# FuenteSim.net
KiCad netlist of a schematic drawn in Altium Designer
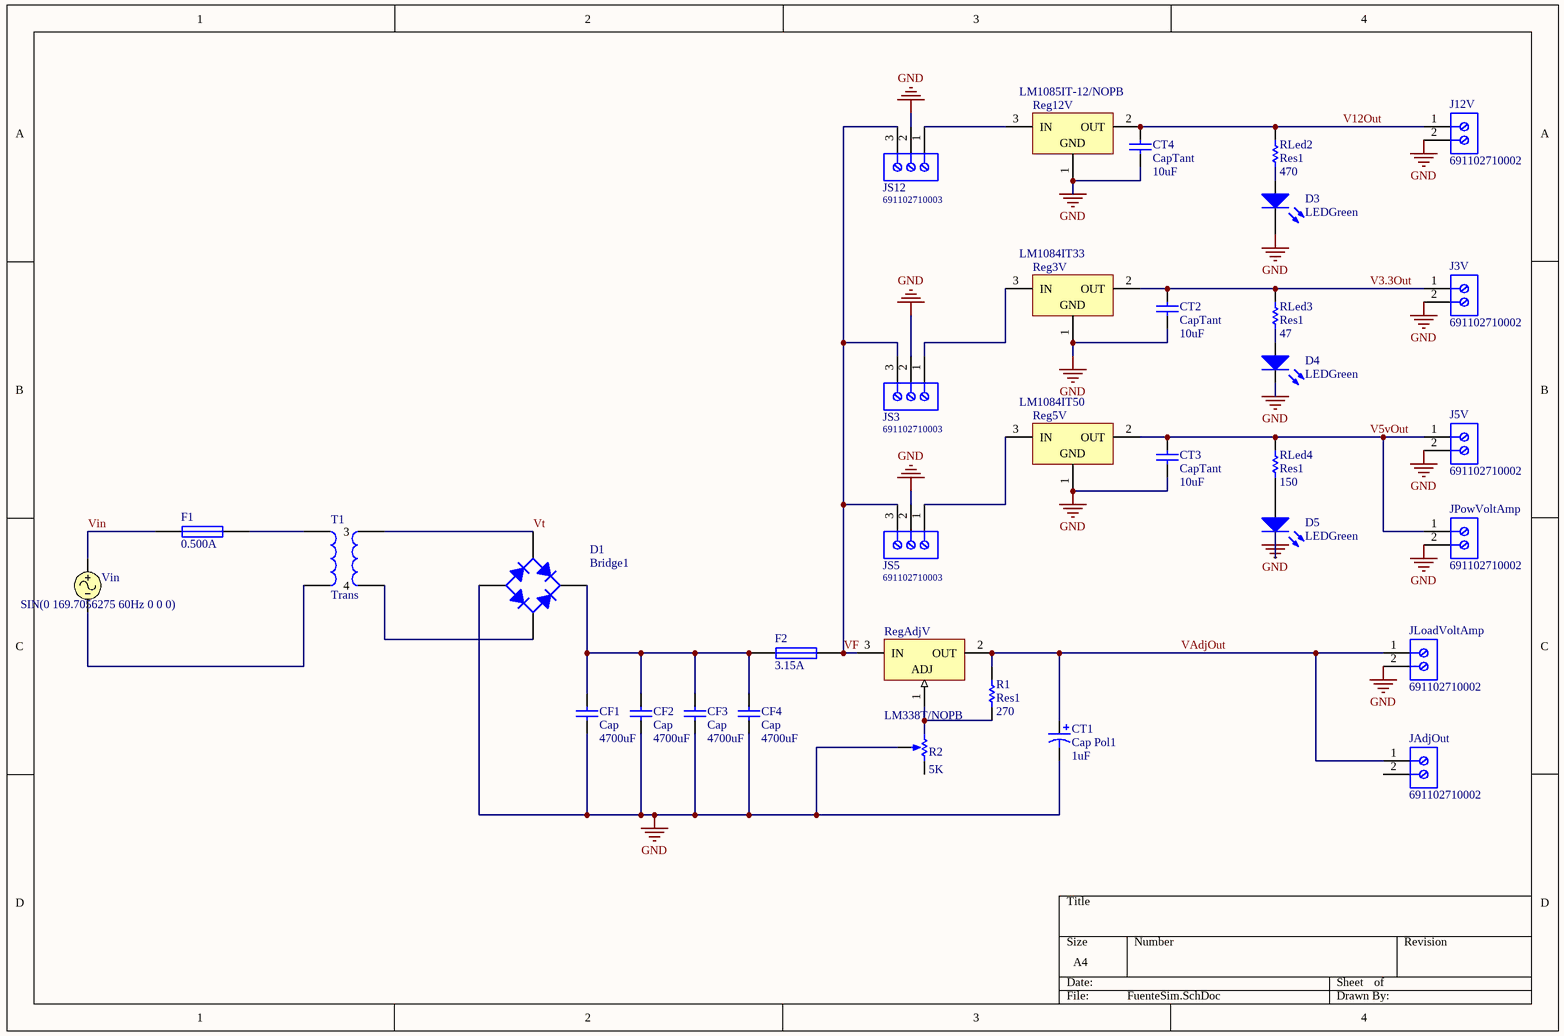
[diagram p0: FuenteSim.SchDoc]

(export (version "E")
  (design (tool "Eeschema 10.0.6"))
  (components
    (comp (ref "CF1")
      (value "Cap")
      (footprint "4700uF")
      (description "Capacitor")
      (fields (field (name "ALTIUM_VALUE") "4700uF") (field (name "PUBLISHER") "Altium Limited"))
      (libsource (lib "Miscellaneous Devices") (part "Cap"))
    )
    (comp (ref "CF2")
      (value "Cap")
      (footprint "4700uF")
      (description "Capacitor")
      (fields (field (name "ALTIUM_VALUE") "4700uF") (field (name "PUBLISHER") "Altium Limited"))
      (libsource (lib "Miscellaneous Devices") (part "Cap"))
    )
    (comp (ref "CF3")
      (value "Cap")
      (footprint "4700uF")
      (description "Capacitor")
      (fields (field (name "ALTIUM_VALUE") "4700uF") (field (name "PUBLISHER") "Altium Limited"))
      (libsource (lib "Miscellaneous Devices") (part "Cap"))
    )
    (comp (ref "CF4")
      (value "Cap")
      (footprint "4700uF")
      (description "Capacitor")
      (fields (field (name "ALTIUM_VALUE") "4700uF") (field (name "PUBLISHER") "Altium Limited"))
      (libsource (lib "Miscellaneous Devices") (part "Cap"))
    )
    (comp (ref "CT1")
      (value "Cap Pol1")
      (footprint "CAPPRD200W50D500H1250")
      (description "Polarized Capacitor (Radial)")
      (fields (field (name "ALTIUM_VALUE") "1uF") (field (name "PUBLISHER") "Altium Limited"))
      (libsource (lib "Miscellaneous Devices") (part "Cap Pol1"))
    )
    (comp (ref "CT2")
      (value "CapTant")
      (footprint "RAD-0.3")
      (description "Capacitor")
      (fields (field (name "ALTIUM_VALUE") "10uF") (field (name "PUBLISHER") "Altium Limited"))
      (libsource (lib "Miscellaneous Devices") (part "Cap"))
    )
    (comp (ref "CT3")
      (value "CapTant")
      (footprint "RAD-0.3")
      (description "Capacitor")
      (fields (field (name "ALTIUM_VALUE") "10uF") (field (name "PUBLISHER") "Altium Limited"))
      (libsource (lib "Miscellaneous Devices") (part "Cap"))
    )
    (comp (ref "CT4")
      (value "CapTant")
      (footprint "RAD-0.3")
      (description "Capacitor")
      (fields (field (name "ALTIUM_VALUE") "10uF") (field (name "PUBLISHER") "Altium Limited"))
      (libsource (lib "Miscellaneous Devices") (part "Cap"))
    )
    (comp (ref "D1")
      (value "Bridge1")
      (footprint "DIOB_GBJ2510")
      (description "Full Wave Diode Bridge")
      (fields (field (name "PUBLISHER") "Altium Limited"))
      (libsource (lib "Miscellaneous Devices") (part "Bridge1"))
    )
    (comp (ref "D3")
      (value "LEDGreen")
      (footprint "LEDRD254W57D500H1070")
      (description "Typical RED, GREEN, YELLOW, AMBER GaAs LED")
      (fields (field (name "PUBLISHER") "Altium Limited"))
      (libsource (lib "Miscellaneous Devices") (part "LED2"))
    )
    (comp (ref "D4")
      (value "LEDGreen")
      (footprint "LEDRD254W57D500H1070")
      (description "Typical RED, GREEN, YELLOW, AMBER GaAs LED")
      (fields (field (name "PUBLISHER") "Altium Limited"))
      (libsource (lib "Miscellaneous Devices") (part "LED2"))
    )
    (comp (ref "D5")
      (value "LEDGreen")
      (footprint "LEDRD254W57D500H1070")
      (description "Typical RED, GREEN, YELLOW, AMBER GaAs LED")
      (fields (field (name "PUBLISHER") "Altium Limited"))
      (libsource (lib "Miscellaneous Devices") (part "LED2"))
    )
    (comp (ref "F1")
      (value "0.500A")
      (footprint "PIN-W2/E2.8")
      (description "Fuse")
      (fields (field (name "PUBLISHER") "Altium Limited"))
      (libsource (lib "Miscellaneous Devices") (part "Fuse 1"))
    )
    (comp (ref "F2")
      (value "3.15A")
      (footprint "PIN-W2/E2.8")
      (fields (field (name "PUBLISHER") "Altium Limited"))
      (libsource (lib "Miscellaneous Devices") (part "Fuse 1"))
    )
    (comp (ref "J3V")
      (value "691102710002")
      (footprint "691102710002")
      (description "Series 102 - 5.00 mm Horizontal Entry Modular with Pressure Clamp WR-TBL, 2 pin")
      (fields (field (name "MANUFACTURER") "Wurth Elektronik") (field (name "PUBLISHER") "WurthElektronik"))
      (libsource (lib "Altium Content Vault") (part "WE-CN-1P-F-TB2"))
    )
    (comp (ref "J5V")
      (value "691102710002")
      (footprint "691102710002")
      (description "Series 102 - 5.00 mm Horizontal Entry Modular with Pressure Clamp WR-TBL, 2 pin")
      (fields (field (name "MANUFACTURER") "Wurth Elektronik") (field (name "PUBLISHER") "WurthElektronik"))
      (libsource (lib "Altium Content Vault") (part "WE-CN-1P-F-TB2"))
    )
    (comp (ref "J12V")
      (value "691102710002")
      (footprint "691102710002")
      (description "Series 102 - 5.00 mm Horizontal Entry Modular with Pressure Clamp WR-TBL, 2 pin")
      (fields (field (name "MANUFACTURER") "Wurth Elektronik") (field (name "PUBLISHER") "WurthElektronik"))
      (libsource (lib "Altium Content Vault") (part "WE-CN-1P-F-TB2"))
    )
    (comp (ref "JAdjOut")
      (value "691102710002")
      (footprint "691102710002")
      (description "Series 102 - 5.00 mm Horizontal Entry Modular with Pressure Clamp WR-TBL, 2 pin")
      (fields (field (name "MANUFACTURER") "Wurth Elektronik") (field (name "PUBLISHER") "WurthElektronik"))
      (libsource (lib "Altium Content Vault") (part "WE-CN-1P-F-TB2"))
    )
    (comp (ref "JLoadVoltAmp")
      (value "691102710002")
      (footprint "691102710002")
      (description "Series 102 - 5.00 mm Horizontal Entry Modular with Pressure Clamp WR-TBL, 2 pin")
      (fields (field (name "MANUFACTURER") "Wurth Elektronik") (field (name "PUBLISHER") "WurthElektronik"))
      (libsource (lib "Altium Content Vault") (part "WE-CN-1P-F-TB2"))
    )
    (comp (ref "JPowVoltAmp")
      (value "691102710002")
      (footprint "691102710002")
      (description "Series 102 - 5.00 mm Horizontal Entry Modular with Pressure Clamp WR-TBL, 2 pin")
      (fields (field (name "MANUFACTURER") "Wurth Elektronik") (field (name "PUBLISHER") "WurthElektronik"))
      (libsource (lib "Altium Content Vault") (part "WE-CN-1P-F-TB2"))
    )
    (comp (ref "JS3")
      (value "691102710003")
      (footprint "691102710003")
      (description "Series 102 - 5.00 mm Horizontal Entry Modular with Pressure Clamp WR-TBL, 3 pin")
      (fields (field (name "MANUFACTURER") "Wurth Elektronik") (field (name "PUBLISHER") "WurthElektronik"))
      (libsource (lib "Altium Content Vault") (part "WE-CN-1P-F-TB3"))
    )
    (comp (ref "JS5")
      (value "691102710003")
      (footprint "691102710003")
      (description "Series 102 - 5.00 mm Horizontal Entry Modular with Pressure Clamp WR-TBL, 3 pin")
      (fields (field (name "MANUFACTURER") "Wurth Elektronik") (field (name "PUBLISHER") "WurthElektronik"))
      (libsource (lib "Altium Content Vault") (part "WE-CN-1P-F-TB3"))
    )
    (comp (ref "JS12")
      (value "691102710003")
      (footprint "691102710003")
      (description "Series 102 - 5.00 mm Horizontal Entry Modular with Pressure Clamp WR-TBL, 3 pin")
      (fields (field (name "MANUFACTURER") "Wurth Elektronik") (field (name "PUBLISHER") "WurthElektronik"))
      (libsource (lib "Altium Content Vault") (part "WE-CN-1P-F-TB3"))
    )
    (comp (ref "R1")
      (value "Res1")
      (footprint "AXIAL-0.3")
      (description "Resistor")
      (fields (field (name "ALTIUM_VALUE") "270") (field (name "PUBLISHER") "Altium Limited"))
      (libsource (lib "Miscellaneous Devices") (part "Res1"))
    )
    (comp (ref "R2")
      (value "5K")
      (description "Potentiometer")
      (libsource (lib "Simulation Generic Components") (part "Potentiometer"))
    )
    (comp (ref "Reg3V")
      (value "LM1084IT33")
      (footprint "NDE0003A")
      (description "5A Low Dropout Positive Regulators, 3-pin TO-220, Pb-Free")
      (fields (field (name "MANUFACTURER") "Texas Instruments"))
      (libsource (lib "Altium Content Vault") (part "PM-REG-LM1086-SIL3"))
    )
    (comp (ref "Reg5V")
      (value "LM1084IT50")
      (footprint "NDE0003A")
      (description "5A Low Dropout Positive Regulators, 3-pin TO-220, Pb-Free")
      (fields (field (name "MANUFACTURER") "Texas Instruments"))
      (libsource (lib "Altium Content Vault") (part "PM-REG-LM1086-SIL3"))
    )
    (comp (ref "Reg12V")
      (value "LM1085IT-12/NOPB")
      (footprint "NDE0003A")
      (description "3A Low Dropout Positive Regulators, 3-pin TO-220, Pb-Free")
      (fields (field (name "MANUFACTURER") "Texas Instruments"))
      (libsource (lib "Altium Content Vault") (part "PM-REG-LM1086-SIL3"))
    )
    (comp (ref "RegAdjV")
      (value "LM338T/NOPB")
      (footprint "NDE0003A")
      (description "5 Amp Adjustable Regulator, 3-pin TO-220, Pb-Free")
      (fields (field (name "MANUFACTURER") "Texas Instruments"))
      (libsource (lib "Altium Content Vault") (part "PM-REG-LM1086ADJ-SIL3"))
    )
    (comp (ref "RLed2")
      (value "Res1")
      (footprint "AXIAL-0.3")
      (description "Resistor")
      (fields (field (name "ALTIUM_VALUE") "470") (field (name "PUBLISHER") "Altium Limited"))
      (libsource (lib "Miscellaneous Devices") (part "Res1"))
    )
    (comp (ref "RLed3")
      (value "Res1")
      (footprint "AXIAL-0.3")
      (description "Resistor")
      (fields (field (name "ALTIUM_VALUE") "47") (field (name "PUBLISHER") "Altium Limited"))
      (libsource (lib "Miscellaneous Devices") (part "Res1"))
    )
    (comp (ref "RLed4")
      (value "Res1")
      (footprint "AXIAL-0.3")
      (description "Resistor")
      (fields (field (name "ALTIUM_VALUE") "150") (field (name "PUBLISHER") "Altium Limited"))
      (libsource (lib "Miscellaneous Devices") (part "Res1"))
    )
    (comp (ref "T1")
      (value "Trans")
      (footprint "691102710002")
      (description "Transformer")
      (fields (field (name "PUBLISHER") "Altium Limited"))
      (libsource (lib "Miscellaneous Devices") (part "Trans"))
    )
    (comp (ref "Vin")
      (value "SIN(0 169.7056275 60Hz 0 0 0)")
      (description "Sinusoidal Voltage Source")
      (fields (field (name "PUBLISHER") "Altium Limited"))
      (libsource (lib "Simulation Sources") (part "VSIN"))
    )
  )
  (nets
    (net (code "1") (name "/V3.3Out") (class "Default")
      (node (ref "CT2") (pin "2") (pinfunction "2_2") (pintype "passive"))
      (node (ref "J3V") (pin "1") (pinfunction "1_1") (pintype "passive"))
      (node (ref "RLed3") (pin "2") (pinfunction "2_2") (pintype "passive"))
      (node (ref "Reg3V") (pin "2") (pinfunction "OUT_2") (pintype "power_in"))
    )
    (net (code "2") (name "/V5vOut") (class "Default")
      (node (ref "CT3") (pin "2") (pinfunction "2_2") (pintype "passive"))
      (node (ref "J5V") (pin "1") (pinfunction "1_1") (pintype "passive"))
      (node (ref "JPowVoltAmp") (pin "1") (pinfunction "1_1") (pintype "passive"))
      (node (ref "RLed4") (pin "2") (pinfunction "2_2") (pintype "passive"))
      (node (ref "Reg5V") (pin "2") (pinfunction "OUT_2") (pintype "power_in"))
    )
    (net (code "3") (name "/V12Out") (class "Default")
      (node (ref "CT4") (pin "2") (pinfunction "2_2") (pintype "passive"))
      (node (ref "J12V") (pin "1") (pinfunction "1_1") (pintype "passive"))
      (node (ref "RLed2") (pin "2") (pinfunction "2_2") (pintype "passive"))
      (node (ref "Reg12V") (pin "2") (pinfunction "OUT_2") (pintype "power_in"))
    )
    (net (code "4") (name "/VAdjOut") (class "Default")
      (node (ref "CT1") (pin "1") (pinfunction "1_1") (pintype "passive"))
      (node (ref "JAdjOut") (pin "1") (pinfunction "1_1") (pintype "passive"))
      (node (ref "JLoadVoltAmp") (pin "1") (pinfunction "1_1") (pintype "passive"))
      (node (ref "R1") (pin "2") (pinfunction "2_2") (pintype "passive"))
      (node (ref "RegAdjV") (pin "2") (pinfunction "OUT_2") (pintype "power_in"))
    )
    (net (code "5") (name "/VF") (class "Default")
      (node (ref "F2") (pin "2") (pinfunction "2_2") (pintype "passive"))
      (node (ref "JS12") (pin "3") (pinfunction "3_3") (pintype "passive"))
      (node (ref "JS3") (pin "3") (pinfunction "3_3") (pintype "passive"))
      (node (ref "JS5") (pin "3") (pinfunction "3_3") (pintype "passive"))
      (node (ref "RegAdjV") (pin "3") (pinfunction "IN_3") (pintype "power_in"))
    )
    (net (code "6") (name "/Vin") (class "Default")
      (node (ref "F1") (pin "1") (pinfunction "1_1") (pintype "passive"))
      (node (ref "Vin") (pin "1") (pinfunction "1_1") (pintype "passive"))
    )
    (net (code "7") (name "/Vt") (class "Default")
      (node (ref "D1") (pin "4") (pinfunction "C_4") (pintype "passive"))
      (node (ref "T1") (pin "3") (pinfunction "3_3") (pintype "passive"))
    )
    (net (code "8") (name "GND") (class "Default")
      (node (ref "CF1") (pin "1") (pinfunction "1_1") (pintype "passive"))
      (node (ref "CF2") (pin "1") (pinfunction "1_1") (pintype "passive"))
      (node (ref "CF3") (pin "1") (pinfunction "1_1") (pintype "passive"))
      (node (ref "CF4") (pin "1") (pinfunction "1_1") (pintype "passive"))
      (node (ref "CT1") (pin "2") (pinfunction "2_2") (pintype "passive"))
      (node (ref "CT2") (pin "1") (pinfunction "1_1") (pintype "passive"))
      (node (ref "CT3") (pin "1") (pinfunction "1_1") (pintype "passive"))
      (node (ref "CT4") (pin "1") (pinfunction "1_1") (pintype "passive"))
      (node (ref "D1") (pin "3") (pinfunction "A_3") (pintype "passive"))
      (node (ref "D3") (pin "2") (pinfunction "K_2") (pintype "passive"))
      (node (ref "D4") (pin "2") (pinfunction "K_2") (pintype "passive"))
      (node (ref "D5") (pin "2") (pinfunction "K_2") (pintype "passive"))
      (node (ref "J12V") (pin "2") (pinfunction "2_2") (pintype "passive"))
      (node (ref "J3V") (pin "2") (pinfunction "2_2") (pintype "passive"))
      (node (ref "J5V") (pin "2") (pinfunction "2_2") (pintype "passive"))
      (node (ref "JLoadVoltAmp") (pin "2") (pinfunction "2_2") (pintype "passive"))
      (node (ref "JPowVoltAmp") (pin "2") (pinfunction "2_2") (pintype "passive"))
      (node (ref "JS12") (pin "2") (pinfunction "2_2") (pintype "passive"))
      (node (ref "JS3") (pin "2") (pinfunction "2_2") (pintype "passive"))
      (node (ref "JS5") (pin "2") (pinfunction "2_2") (pintype "passive"))
      (node (ref "R2") (pin "3") (pinfunction "TAP_3") (pintype "passive"))
      (node (ref "Reg12V") (pin "1") (pinfunction "GND_1") (pintype "power_in"))
      (node (ref "Reg3V") (pin "1") (pinfunction "GND_1") (pintype "power_in"))
      (node (ref "Reg5V") (pin "1") (pinfunction "GND_1") (pintype "power_in"))
    )
    (net (code "9") (name "Net-(D1-C-Pad2)") (class "Default")
      (node (ref "D1") (pin "2") (pinfunction "C_2") (pintype "passive"))
      (node (ref "T1") (pin "4") (pinfunction "4_4") (pintype "passive"))
    )
    (net (code "10") (name "Net-(D1-K)") (class "Default")
      (node (ref "CF1") (pin "2") (pinfunction "2_2") (pintype "passive"))
      (node (ref "CF2") (pin "2") (pinfunction "2_2") (pintype "passive"))
      (node (ref "CF3") (pin "2") (pinfunction "2_2") (pintype "passive"))
      (node (ref "CF4") (pin "2") (pinfunction "2_2") (pintype "passive"))
      (node (ref "D1") (pin "1") (pinfunction "K_1") (pintype "passive"))
      (node (ref "F2") (pin "1") (pinfunction "1_1") (pintype "passive"))
    )
    (net (code "11") (name "Net-(D3-A)") (class "Default")
      (node (ref "D3") (pin "1") (pinfunction "A_1") (pintype "passive"))
      (node (ref "RLed2") (pin "1") (pinfunction "1_1") (pintype "passive"))
    )
    (net (code "12") (name "Net-(D4-A)") (class "Default")
      (node (ref "D4") (pin "1") (pinfunction "A_1") (pintype "passive"))
      (node (ref "RLed3") (pin "1") (pinfunction "1_1") (pintype "passive"))
    )
    (net (code "13") (name "Net-(D5-A)") (class "Default")
      (node (ref "D5") (pin "1") (pinfunction "A_1") (pintype "passive"))
      (node (ref "RLed4") (pin "1") (pinfunction "1_1") (pintype "passive"))
    )
    (net (code "14") (name "Net-(F1-Pad2)") (class "Default")
      (node (ref "F1") (pin "2") (pinfunction "2_2") (pintype "passive"))
      (node (ref "T1") (pin "1") (pinfunction "1_1") (pintype "passive"))
    )
    (net (code "15") (name "Net-(R2-TOP)") (class "Default")
      (node (ref "R1") (pin "1") (pinfunction "1_1") (pintype "passive"))
      (node (ref "R2") (pin "1") (pinfunction "TOP_1") (pintype "passive"))
      (node (ref "RegAdjV") (pin "1") (pinfunction "ADJ_1") (pintype "input"))
    )
    (net (code "16") (name "Net-(Reg3V-IN)") (class "Default")
      (node (ref "JS3") (pin "1") (pinfunction "1_1") (pintype "passive"))
      (node (ref "Reg3V") (pin "3") (pinfunction "IN_3") (pintype "power_in"))
    )
    (net (code "17") (name "Net-(Reg5V-IN)") (class "Default")
      (node (ref "JS5") (pin "1") (pinfunction "1_1") (pintype "passive"))
      (node (ref "Reg5V") (pin "3") (pinfunction "IN_3") (pintype "power_in"))
    )
    (net (code "18") (name "Net-(Reg12V-IN)") (class "Default")
      (node (ref "JS12") (pin "1") (pinfunction "1_1") (pintype "passive"))
      (node (ref "Reg12V") (pin "3") (pinfunction "IN_3") (pintype "power_in"))
    )
    (net (code "19") (name "Net-(T1-Pad2)") (class "Default")
      (node (ref "T1") (pin "2") (pinfunction "2_2") (pintype "passive"))
      (node (ref "Vin") (pin "2") (pinfunction "2_2") (pintype "passive"))
    )
    (net (code "20") (name "unconnected-(JAdjOut-Pad2)") (class "Default")
      (node (ref "JAdjOut") (pin "2") (pinfunction "2_2") (pintype "passive"))
    )
    (net (code "21") (name "unconnected-(R2-BOT-Pad2)") (class "Default")
      (node (ref "R2") (pin "2") (pinfunction "BOT_2") (pintype "passive"))
    )
  )
)
